# NewPCBMC.net
KiCad netlist of a schematic drawn in Altium Designer
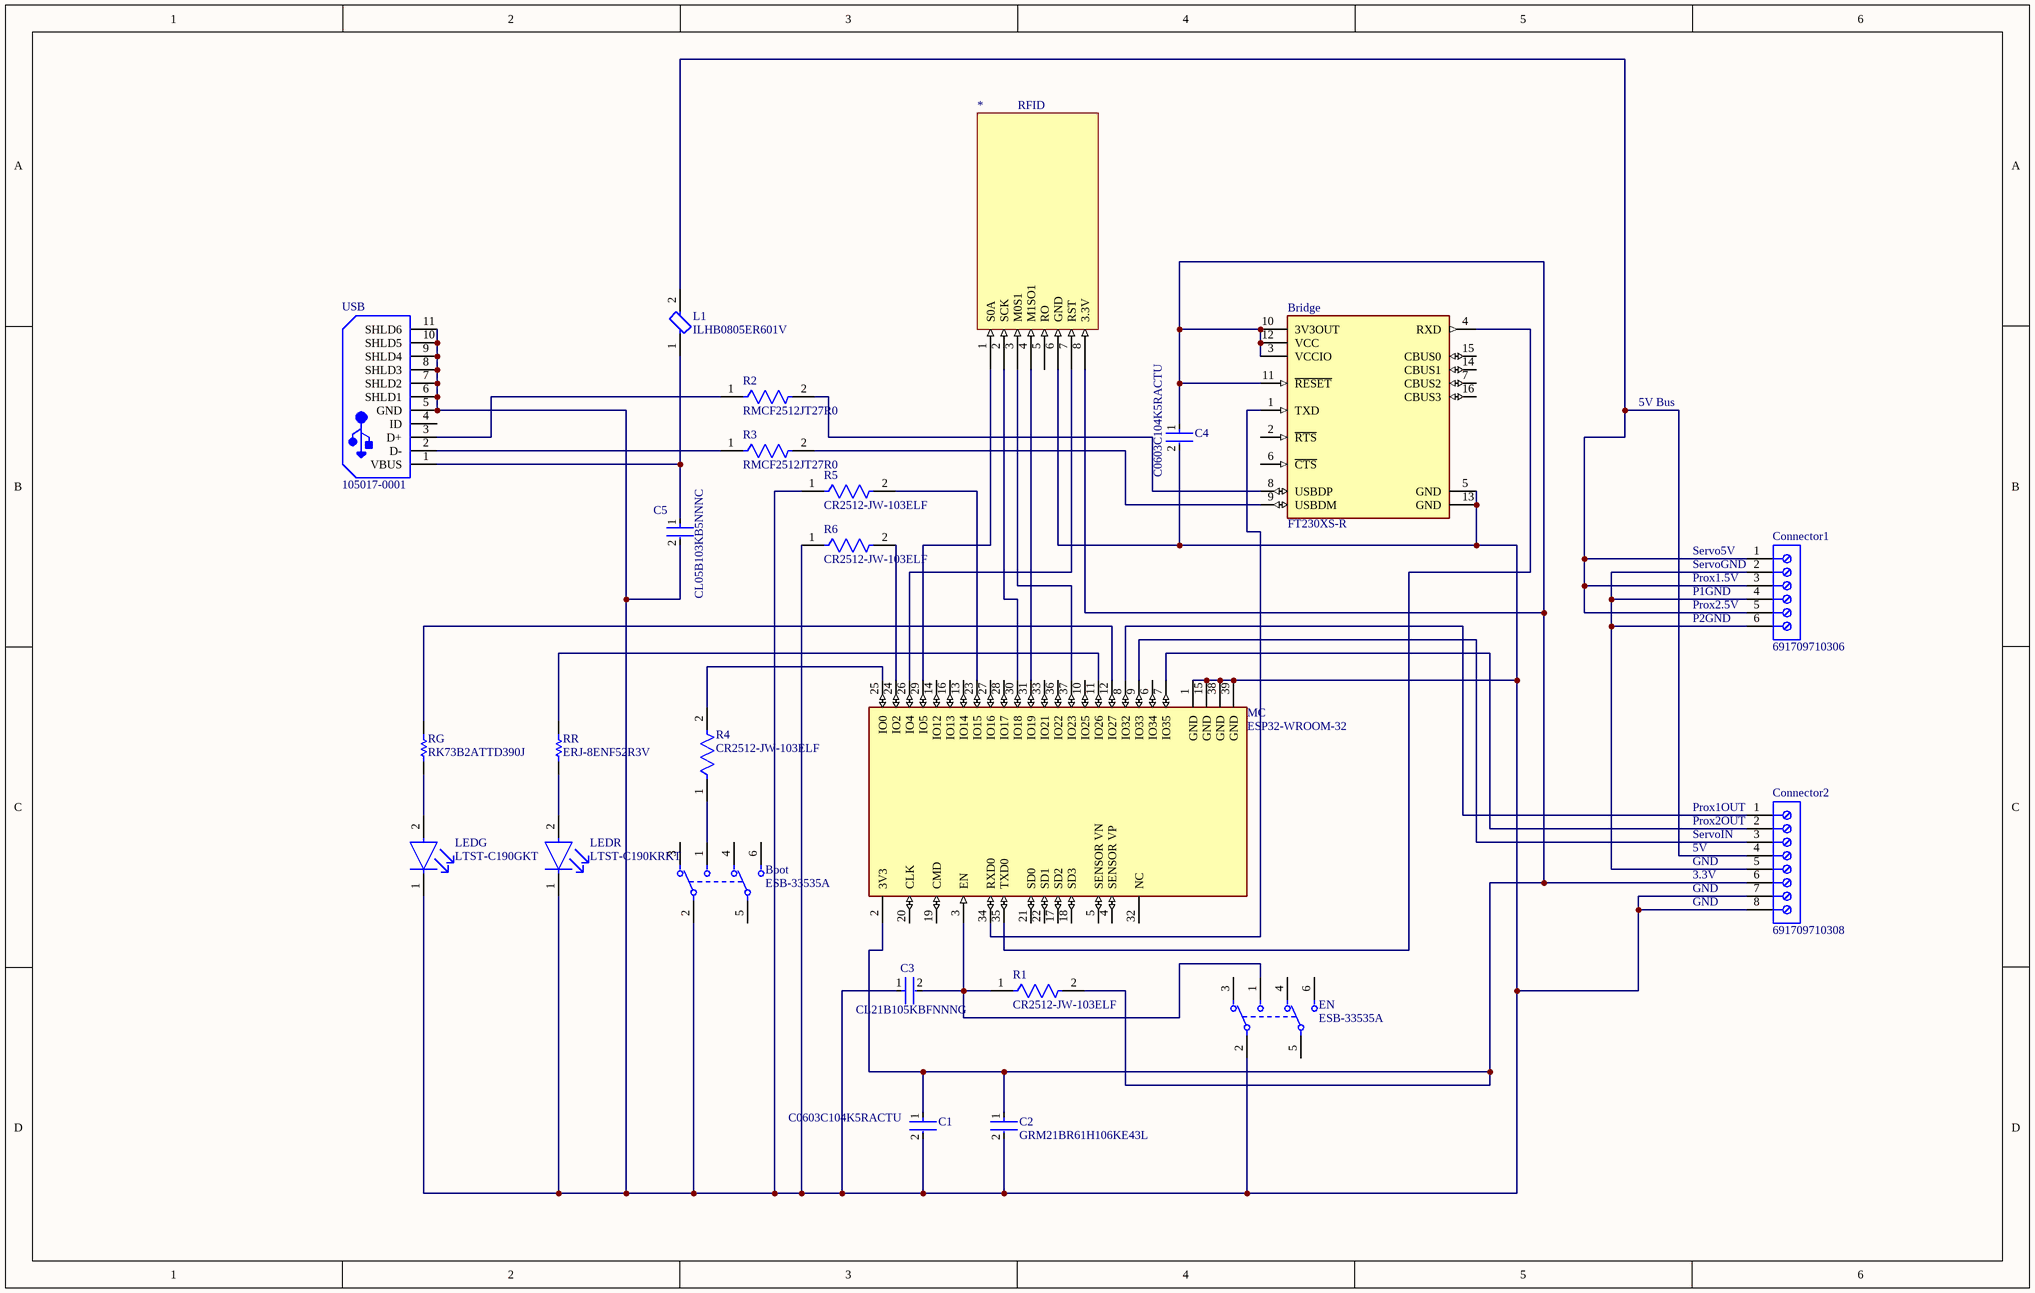
[diagram p0: NewPCBMC.SchDoc]

(export (version "E")
  (design (tool "Eeschema 10.0.6"))
  (components
    (comp (ref "*")
      (value "RFID")
      (footprint "PCBComponent_1")
      (libsource (lib "ProxLibLib") (part "Component_1"))
    )
    (comp (ref "Boot")
      (value "ESB-33535A")
      (footprint "FP-ESB-33535A-MFG")
      (description "SWITCH PUSH DPDT 0.2A 14V")
      (libsource (lib "Altium Content Vault") (part "44dd61f6fe09eb68f0782b479c50d43"))
    )
    (comp (ref "Bridge")
      (value "FT230XS-R")
      (footprint "FP-SSOP-16-MFG")
      (description "IC USB SERIAL BASIC UART 16SSOP")
      (libsource (lib "Altium Content Vault") (part "33f179d67b5e33a3acba2e4c59411a5"))
    )
    (comp (ref "C1")
      (value "C0603C104K5RACTU")
      (footprint "FP-C0603C-CF-MFG")
      (description "CAP CER 0.1UF 50V X7R 0603")
      (fields (field (name "TOLERANCE") "0.1") (field (name "MANUFACTURER") "KEMET"))
      (libsource (lib "Altium Content Vault") (part "b4654b650e69147ec39a6b967a45e02"))
    )
    (comp (ref "C2")
      (value "GRM21BR61H106KE43L")
      (footprint "FP-GRM21B-0_2-e0_2_0_7-IPC_A")
      (description "Chip Multilayer Ceramic Capacitors for General Purpose, 0805, 10uF, X5R, 15%, 10%, 50V")
      (fields (field (name "TOLERANCE") "10%"))
      (libsource (lib "Altium Content Vault") (part "b4654b650e69147ec39a6b967a45e02"))
    )
    (comp (ref "C3")
      (value "CL21B105KBFNNNG")
      (footprint "FP-CL21-IPC_C")
      (description "CL21 Series 0805 1uF 50V ±10% Tolerance X7R Multilayer Ceramic Chip Capacitor")
      (fields (field (name "VOLTAGE") "50V") (field (name "TOLERANCE") "10%"))
      (libsource (lib "Altium Content Vault") (part "b4654b650e69147ec39a6b967a45e02"))
    )
    (comp (ref "C4")
      (value "C0603C104K5RACTU")
      (footprint "FP-C0603C-CF-MFG")
      (description "CAP CER 0.1UF 50V X7R 0603")
      (fields (field (name "TOLERANCE") "0.1") (field (name "MANUFACTURER") "KEMET"))
      (libsource (lib "Altium Content Vault") (part "b4654b650e69147ec39a6b967a45e02"))
    )
    (comp (ref "C5")
      (value "CL05B103KB5NNNC")
      (footprint "FP-CL165-IPC_C")
      (description "Cap Ceramic 10nF 50V X7R ±10% SMD 0402 +125°C Paper T/R")
      (fields (field (name "VOLTAGE") "50V") (field (name "TOLERANCE") "10%"))
      (libsource (lib "Altium Content Vault") (part "b4654b650e69147ec39a6b967a45e02"))
    )
    (comp (ref "Connector1")
      (value "691709710306")
      (footprint "691709710306")
      (fields (field (name "VOLTAGE") "300V"))
      (libsource (lib "Altium Content Vault") (part "TBL - 1R - 06P - Screw"))
    )
    (comp (ref "Connector2")
      (value "691709710308")
      (footprint "691709710308")
      (fields (field (name "VOLTAGE") "300V"))
      (libsource (lib "Altium Content Vault") (part "TBL - 1R - 08P - Screw"))
    )
    (comp (ref "EN")
      (value "ESB-33535A")
      (footprint "FP-ESB-33535A-MFG")
      (description "SWITCH PUSH DPDT 0.2A 14V")
      (libsource (lib "Altium Content Vault") (part "44dd61f6fe09eb68f0782b479c50d43"))
    )
    (comp (ref "L1")
      (value "ILHB0805ER601V")
      (footprint "FP-ILHB-0805-IPC_C")
      (description "FERRITE BEAD 600 OHM 0805 1LN")
      (fields
        (field (name "TOLERANCE") "25%")
        (field (name "OCTOPART") "https://octopart.com/ilhb0805er601v-vishay-39650184")
      )
      (libsource (lib "Altium Content Vault") (part "5f30dd21d616792df468990f7003faa"))
    )
    (comp (ref "LEDG")
      (value "LTST-C190GKT")
      (footprint "FP-LTST-C190GKT-MFG")
      (description "LED GREEN CLEAR CHIP SMD")
      (fields (field (name "VOLTAGE") "2V"))
      (libsource (lib "Altium Content Vault") (part "8706943c75ba83719d021d2fdc84c58"))
    )
    (comp (ref "LEDR")
      (value "LTST-C190KRKT")
      (footprint "FP-LTST-C190KRKT-MFG")
      (description "LED RED CLEAR CHIP SMD")
      (libsource (lib "Altium Content Vault") (part "8706943c75ba83719d021d2fdc84c58"))
    )
    (comp (ref "MC")
      (value "ESP32-WROOM-32")
      (footprint "FP-ESP32-WROOM-32-MFG")
      (description "RX TXRX MOD WIFI SURFACE MOUNT")
      (libsource (lib "Altium Content Vault") (part "ee866abf0b6c51247b7f5cdebf2f250"))
    )
    (comp (ref "R1")
      (value "CR2512-JW-103ELF")
      (footprint "FP-CR2512-IPC_B")
      (description "Thick Film Chip Resistors 2512 10kΩ 1W 5% 200ppm/°C")
      (fields (field (name "TOLERANCE") "5%"))
      (libsource (lib "Altium Content Vault") (part "1029c3af85768c4190bb7ad29bc67b5"))
    )
    (comp (ref "R2")
      (value "RMCF2512JT27R0")
      (footprint "FP-RMCF2512-IPC_B")
      (description "27Ω ±5% 1W 2512 Thick Film Chip Resistor AEC-Q200 compliant")
      (fields (field (name "TOLERANCE") "5%"))
      (libsource (lib "Altium Content Vault") (part "1029c3af85768c4190bb7ad29bc67b5"))
    )
    (comp (ref "R3")
      (value "RMCF2512JT27R0")
      (footprint "FP-RMCF2512-IPC_B")
      (description "27Ω ±5% 1W 2512 Thick Film Chip Resistor AEC-Q200 compliant")
      (fields (field (name "TOLERANCE") "5%"))
      (libsource (lib "Altium Content Vault") (part "1029c3af85768c4190bb7ad29bc67b5"))
    )
    (comp (ref "R4")
      (value "CR2512-JW-103ELF")
      (footprint "FP-CR2512-IPC_B")
      (description "Thick Film Chip Resistors 2512 10kΩ 1W 5% 200ppm/°C")
      (fields (field (name "TOLERANCE") "5%"))
      (libsource (lib "Altium Content Vault") (part "1029c3af85768c4190bb7ad29bc67b5"))
    )
    (comp (ref "R5")
      (value "CR2512-JW-103ELF")
      (footprint "FP-CR2512-IPC_B")
      (description "Thick Film Chip Resistors 2512 10kΩ 1W 5% 200ppm/°C")
      (fields (field (name "TOLERANCE") "5%"))
      (libsource (lib "Altium Content Vault") (part "1029c3af85768c4190bb7ad29bc67b5"))
    )
    (comp (ref "R6")
      (value "CR2512-JW-103ELF")
      (footprint "FP-CR2512-IPC_B")
      (description "Thick Film Chip Resistors 2512 10kΩ 1W 5% 200ppm/°C")
      (fields (field (name "TOLERANCE") "5%"))
      (libsource (lib "Altium Content Vault") (part "1029c3af85768c4190bb7ad29bc67b5"))
    )
    (comp (ref "RG")
      (value "RK73B2ATTD390J")
      (footprint "RESC2013X60X30ML20T20")
      (fields (field (name "MANUFACTURER") "KOA Speer"))
      (libsource (lib "Altium Content Vault") (part "RES"))
    )
    (comp (ref "RR")
      (value "ERJ-8ENF52R3V")
      (footprint "RESC3216X70X50NL05T20")
      (fields (field (name "MANUFACTURER") "Panasonic"))
      (libsource (lib "Altium Content Vault") (part "RES"))
    )
    (comp (ref "USB")
      (value "105017-0001")
      (footprint "USB-MICRO-B_V")
      (fields (field (name "MANUFACTURER") "Molex"))
      (libsource (lib "Altium Content Vault") (part "USB-5-6SHLD"))
    )
  )
  (nets
    (net (code "1") (name "Net-(*-3.3V)") (class "Default")
      (node (ref "*") (pin "8") (pinfunction "3.3V_8") (pintype "input"))
      (node (ref "Bridge") (pin "10") (pinfunction "3V3OUT_10") (pintype "power_in"))
      (node (ref "Bridge") (pin "11") (pinfunction "~{RESET}_11") (pintype "input"))
      (node (ref "Bridge") (pin "12") (pinfunction "VCC_12") (pintype "power_in"))
      (node (ref "Bridge") (pin "3") (pinfunction "VCCIO_3") (pintype "power_in"))
      (node (ref "C1") (pin "1") (pinfunction "1_1") (pintype "passive"))
      (node (ref "C2") (pin "1") (pinfunction "1_1") (pintype "passive"))
      (node (ref "C4") (pin "1") (pinfunction "1_1") (pintype "passive"))
      (node (ref "Connector2") (pin "6") (pinfunction "6_6") (pintype "passive"))
      (node (ref "MC") (pin "2") (pinfunction "3V3_2") (pintype "power_in"))
      (node (ref "R1") (pin "2") (pinfunction "2_2") (pintype "passive"))
    )
    (net (code "2") (name "Net-(*-GND)") (class "Default")
      (node (ref "*") (pin "6") (pinfunction "GND_6") (pintype "input"))
      (node (ref "Boot") (pin "2") (pinfunction "1_C_2") (pintype "passive"))
      (node (ref "Bridge") (pin "13") (pinfunction "GND_13") (pintype "power_in"))
      (node (ref "Bridge") (pin "5") (pinfunction "GND_5") (pintype "power_in"))
      (node (ref "C1") (pin "2") (pinfunction "2_2") (pintype "passive"))
      (node (ref "C2") (pin "2") (pinfunction "2_2") (pintype "passive"))
      (node (ref "C3") (pin "1") (pinfunction "1_1") (pintype "passive"))
      (node (ref "C4") (pin "2") (pinfunction "2_2") (pintype "passive"))
      (node (ref "C5") (pin "2") (pinfunction "2_2") (pintype "passive"))
      (node (ref "Connector2") (pin "7") (pinfunction "7_7") (pintype "passive"))
      (node (ref "Connector2") (pin "8") (pinfunction "8_8") (pintype "passive"))
      (node (ref "EN") (pin "2") (pinfunction "1_C_2") (pintype "passive"))
      (node (ref "LEDG") (pin "1") (pinfunction "C_1") (pintype "passive"))
      (node (ref "LEDR") (pin "1") (pinfunction "C_1") (pintype "passive"))
      (node (ref "MC") (pin "1") (pinfunction "GND_1") (pintype "power_in"))
      (node (ref "MC") (pin "15") (pinfunction "GND_15") (pintype "power_in"))
      (node (ref "MC") (pin "38") (pinfunction "GND_38") (pintype "power_in"))
      (node (ref "MC") (pin "39") (pinfunction "GND_39") (pintype "power_in"))
      (node (ref "R5") (pin "1") (pinfunction "1_1") (pintype "passive"))
      (node (ref "R6") (pin "1") (pinfunction "1_1") (pintype "passive"))
      (node (ref "USB") (pin "10") (pinfunction "SHLD5_10") (pintype "passive"))
      (node (ref "USB") (pin "11") (pinfunction "SHLD6_11") (pintype "passive"))
      (node (ref "USB") (pin "5") (pinfunction "GND_5") (pintype "passive"))
      (node (ref "USB") (pin "6") (pinfunction "SHLD1_6") (pintype "passive"))
      (node (ref "USB") (pin "7") (pinfunction "SHLD2_7") (pintype "passive"))
      (node (ref "USB") (pin "8") (pinfunction "SHLD3_8") (pintype "passive"))
      (node (ref "USB") (pin "9") (pinfunction "SHLD4_9") (pintype "passive"))
    )
    (net (code "3") (name "Net-(*-M0S1)") (class "Default")
      (node (ref "*") (pin "3") (pinfunction "M0S1_3") (pintype "input"))
      (node (ref "MC") (pin "37") (pinfunction "IO23_37") (pintype "bidirectional"))
    )
    (net (code "4") (name "Net-(*-M1SO1)") (class "Default")
      (node (ref "*") (pin "4") (pinfunction "M1SO1_4") (pintype "input"))
      (node (ref "MC") (pin "31") (pinfunction "IO19_31") (pintype "bidirectional"))
    )
    (net (code "5") (name "Net-(*-RST)") (class "Default")
      (node (ref "*") (pin "7") (pinfunction "RST_7") (pintype "input"))
      (node (ref "MC") (pin "26") (pinfunction "IO4_26") (pintype "bidirectional"))
    )
    (net (code "6") (name "Net-(*-S0A)") (class "Default")
      (node (ref "*") (pin "1") (pinfunction "S0A_1") (pintype "input"))
      (node (ref "MC") (pin "29") (pinfunction "IO5_29") (pintype "bidirectional"))
    )
    (net (code "7") (name "Net-(*-SCK)") (class "Default")
      (node (ref "*") (pin "2") (pinfunction "SCK_2") (pintype "input"))
      (node (ref "MC") (pin "30") (pinfunction "IO18_30") (pintype "bidirectional"))
    )
    (net (code "8") (name "Net-(Boot-1_N.O.)") (class "Default")
      (node (ref "Boot") (pin "1") (pinfunction "1_N.O._1") (pintype "passive"))
      (node (ref "R4") (pin "1") (pinfunction "1_1") (pintype "passive"))
    )
    (net (code "9") (name "Net-(Bridge-RXD)") (class "Default")
      (node (ref "Bridge") (pin "4") (pinfunction "RXD_4") (pintype "output"))
      (node (ref "MC") (pin "35") (pinfunction "TXD0_35") (pintype "bidirectional"))
    )
    (net (code "10") (name "Net-(Bridge-TXD)") (class "Default")
      (node (ref "Bridge") (pin "1") (pinfunction "TXD_1") (pintype "input"))
      (node (ref "MC") (pin "34") (pinfunction "RXD0_34") (pintype "bidirectional"))
    )
    (net (code "11") (name "Net-(Bridge-USBDM)") (class "Default")
      (node (ref "Bridge") (pin "9") (pinfunction "USBDM_9") (pintype "bidirectional"))
      (node (ref "R3") (pin "2") (pinfunction "2_2") (pintype "passive"))
    )
    (net (code "12") (name "Net-(Bridge-USBDP)") (class "Default")
      (node (ref "Bridge") (pin "8") (pinfunction "USBDP_8") (pintype "bidirectional"))
      (node (ref "R2") (pin "2") (pinfunction "2_2") (pintype "passive"))
    )
    (net (code "13") (name "Net-(Connector1-Pad1)") (class "Default")
      (node (ref "Connector1") (pin "1") (pinfunction "1_1") (pintype "passive"))
      (node (ref "Connector1") (pin "3") (pinfunction "3_3") (pintype "passive"))
      (node (ref "Connector1") (pin "5") (pinfunction "5_5") (pintype "passive"))
      (node (ref "Connector2") (pin "4") (pinfunction "4_4") (pintype "passive"))
      (node (ref "L1") (pin "2") (pinfunction "2_2") (pintype "passive"))
    )
    (net (code "14") (name "Net-(Connector1-Pad2)") (class "Default")
      (node (ref "Connector1") (pin "2") (pinfunction "2_2") (pintype "passive"))
      (node (ref "Connector1") (pin "4") (pinfunction "4_4") (pintype "passive"))
      (node (ref "Connector1") (pin "6") (pinfunction "6_6") (pintype "passive"))
      (node (ref "Connector2") (pin "5") (pinfunction "5_5") (pintype "passive"))
    )
    (net (code "15") (name "Net-(EN-1_N.O.)") (class "Default")
      (node (ref "C3") (pin "2") (pinfunction "2_2") (pintype "passive"))
      (node (ref "EN") (pin "1") (pinfunction "1_N.O._1") (pintype "passive"))
      (node (ref "MC") (pin "3") (pinfunction "EN_3") (pintype "input"))
      (node (ref "R1") (pin "1") (pinfunction "1_1") (pintype "passive"))
    )
    (net (code "16") (name "Net-(LEDG-A)") (class "Default")
      (node (ref "LEDG") (pin "2") (pinfunction "A_2") (pintype "passive"))
      (node (ref "RG") (pin "1") (pinfunction "1_1") (pintype "passive"))
    )
    (net (code "17") (name "Net-(LEDR-A)") (class "Default")
      (node (ref "LEDR") (pin "2") (pinfunction "A_2") (pintype "passive"))
      (node (ref "RR") (pin "1") (pinfunction "1_1") (pintype "passive"))
    )
    (net (code "18") (name "Net-(MC-IO0)") (class "Default")
      (node (ref "MC") (pin "25") (pinfunction "IO0_25") (pintype "bidirectional"))
      (node (ref "R4") (pin "2") (pinfunction "2_2") (pintype "passive"))
    )
    (net (code "19") (name "Net-(MC-IO2)") (class "Default")
      (node (ref "MC") (pin "24") (pinfunction "IO2_24") (pintype "bidirectional"))
      (node (ref "R6") (pin "2") (pinfunction "2_2") (pintype "passive"))
    )
    (net (code "20") (name "Net-(MC-IO15)") (class "Default")
      (node (ref "MC") (pin "23") (pinfunction "IO15_23") (pintype "bidirectional"))
      (node (ref "R5") (pin "2") (pinfunction "2_2") (pintype "passive"))
    )
    (net (code "21") (name "Net-(MC-IO26)") (class "Default")
      (node (ref "MC") (pin "11") (pinfunction "IO26_11") (pintype "bidirectional"))
      (node (ref "RR") (pin "2") (pinfunction "2_2") (pintype "passive"))
    )
    (net (code "22") (name "Net-(MC-IO27)") (class "Default")
      (node (ref "MC") (pin "12") (pinfunction "IO27_12") (pintype "bidirectional"))
      (node (ref "RG") (pin "2") (pinfunction "2_2") (pintype "passive"))
    )
    (net (code "23") (name "Net-(MC-IO32)") (class "Default")
      (node (ref "Connector2") (pin "1") (pinfunction "1_1") (pintype "passive"))
      (node (ref "MC") (pin "8") (pinfunction "IO32_8") (pintype "bidirectional"))
    )
    (net (code "24") (name "Net-(MC-IO33)") (class "Default")
      (node (ref "Connector2") (pin "3") (pinfunction "3_3") (pintype "passive"))
      (node (ref "MC") (pin "9") (pinfunction "IO33_9") (pintype "bidirectional"))
    )
    (net (code "25") (name "Net-(MC-IO35)") (class "Default")
      (node (ref "Connector2") (pin "2") (pinfunction "2_2") (pintype "passive"))
      (node (ref "MC") (pin "7") (pinfunction "IO35_7") (pintype "bidirectional"))
    )
    (net (code "26") (name "Net-(USB-D+)") (class "Default")
      (node (ref "R2") (pin "1") (pinfunction "1_1") (pintype "passive"))
      (node (ref "USB") (pin "3") (pinfunction "D+_3") (pintype "passive"))
    )
    (net (code "27") (name "Net-(USB-D-)") (class "Default")
      (node (ref "R3") (pin "1") (pinfunction "1_1") (pintype "passive"))
      (node (ref "USB") (pin "2") (pinfunction "D-_2") (pintype "passive"))
    )
    (net (code "28") (name "Net-(USB-VBUS)") (class "Default")
      (node (ref "C5") (pin "1") (pinfunction "1_1") (pintype "passive"))
      (node (ref "L1") (pin "1") (pinfunction "1_1") (pintype "passive"))
      (node (ref "USB") (pin "1") (pinfunction "VBUS_1") (pintype "passive"))
    )
    (net (code "29") (name "unconnected-(*-RO-Pad5)") (class "Default")
      (node (ref "*") (pin "5") (pinfunction "RO_5") (pintype "input"))
    )
    (net (code "30") (name "unconnected-(Boot-1_N.C.-Pad3)") (class "Default")
      (node (ref "Boot") (pin "3") (pinfunction "1_N.C._3") (pintype "passive"))
    )
    (net (code "31") (name "unconnected-(Boot-2_C-Pad5)") (class "Default")
      (node (ref "Boot") (pin "5") (pinfunction "2_C_5") (pintype "passive"))
    )
    (net (code "32") (name "unconnected-(Boot-2_N.C.-Pad4)") (class "Default")
      (node (ref "Boot") (pin "4") (pinfunction "2_N.C._4") (pintype "passive"))
    )
    (net (code "33") (name "unconnected-(Boot-2_N.O.-Pad6)") (class "Default")
      (node (ref "Boot") (pin "6") (pinfunction "2_N.O._6") (pintype "passive"))
    )
    (net (code "34") (name "unconnected-(Bridge-CBUS0-Pad15)") (class "Default")
      (node (ref "Bridge") (pin "15") (pinfunction "CBUS0_15") (pintype "bidirectional"))
    )
    (net (code "35") (name "unconnected-(Bridge-CBUS1-Pad14)") (class "Default")
      (node (ref "Bridge") (pin "14") (pinfunction "CBUS1_14") (pintype "bidirectional"))
    )
    (net (code "36") (name "unconnected-(Bridge-CBUS2-Pad7)") (class "Default")
      (node (ref "Bridge") (pin "7") (pinfunction "CBUS2_7") (pintype "bidirectional"))
    )
    (net (code "37") (name "unconnected-(Bridge-CBUS3-Pad16)") (class "Default")
      (node (ref "Bridge") (pin "16") (pinfunction "CBUS3_16") (pintype "bidirectional"))
    )
    (net (code "38") (name "unconnected-(Bridge-~{CTS}-Pad6)") (class "Default")
      (node (ref "Bridge") (pin "6") (pinfunction "~{CTS}_6") (pintype "input"))
    )
    (net (code "39") (name "unconnected-(Bridge-~{RTS}-Pad2)") (class "Default")
      (node (ref "Bridge") (pin "2") (pinfunction "~{RTS}_2") (pintype "input"))
    )
    (net (code "40") (name "unconnected-(EN-1_N.C.-Pad3)") (class "Default")
      (node (ref "EN") (pin "3") (pinfunction "1_N.C._3") (pintype "passive"))
    )
    (net (code "41") (name "unconnected-(EN-2_C-Pad5)") (class "Default")
      (node (ref "EN") (pin "5") (pinfunction "2_C_5") (pintype "passive"))
    )
    (net (code "42") (name "unconnected-(EN-2_N.C.-Pad4)") (class "Default")
      (node (ref "EN") (pin "4") (pinfunction "2_N.C._4") (pintype "passive"))
    )
    (net (code "43") (name "unconnected-(EN-2_N.O.-Pad6)") (class "Default")
      (node (ref "EN") (pin "6") (pinfunction "2_N.O._6") (pintype "passive"))
    )
    (net (code "44") (name "unconnected-(MC-CLK-Pad20)") (class "Default")
      (node (ref "MC") (pin "20") (pinfunction "CLK_20") (pintype "bidirectional"))
    )
    (net (code "45") (name "unconnected-(MC-CMD-Pad19)") (class "Default")
      (node (ref "MC") (pin "19") (pinfunction "CMD_19") (pintype "bidirectional"))
    )
    (net (code "46") (name "unconnected-(MC-IO12-Pad14)") (class "Default")
      (node (ref "MC") (pin "14") (pinfunction "IO12_14") (pintype "bidirectional"))
    )
    (net (code "47") (name "unconnected-(MC-IO13-Pad16)") (class "Default")
      (node (ref "MC") (pin "16") (pinfunction "IO13_16") (pintype "bidirectional"))
    )
    (net (code "48") (name "unconnected-(MC-IO14-Pad13)") (class "Default")
      (node (ref "MC") (pin "13") (pinfunction "IO14_13") (pintype "bidirectional"))
    )
    (net (code "49") (name "unconnected-(MC-IO16-Pad27)") (class "Default")
      (node (ref "MC") (pin "27") (pinfunction "IO16_27") (pintype "bidirectional"))
    )
    (net (code "50") (name "unconnected-(MC-IO17-Pad28)") (class "Default")
      (node (ref "MC") (pin "28") (pinfunction "IO17_28") (pintype "bidirectional"))
    )
    (net (code "51") (name "unconnected-(MC-IO21-Pad33)") (class "Default")
      (node (ref "MC") (pin "33") (pinfunction "IO21_33") (pintype "bidirectional"))
    )
    (net (code "52") (name "unconnected-(MC-IO22-Pad36)") (class "Default")
      (node (ref "MC") (pin "36") (pinfunction "IO22_36") (pintype "bidirectional"))
    )
    (net (code "53") (name "unconnected-(MC-IO25-Pad10)") (class "Default")
      (node (ref "MC") (pin "10") (pinfunction "IO25_10") (pintype "bidirectional"))
    )
    (net (code "54") (name "unconnected-(MC-IO34-Pad6)") (class "Default")
      (node (ref "MC") (pin "6") (pinfunction "IO34_6") (pintype "bidirectional"))
    )
    (net (code "55") (name "unconnected-(MC-NC-Pad32)") (class "Default")
      (node (ref "MC") (pin "32") (pinfunction "NC_32") (pintype "passive"))
    )
    (net (code "56") (name "unconnected-(MC-SD0-Pad21)") (class "Default")
      (node (ref "MC") (pin "21") (pinfunction "SD0_21") (pintype "bidirectional"))
    )
    (net (code "57") (name "unconnected-(MC-SD1-Pad22)") (class "Default")
      (node (ref "MC") (pin "22") (pinfunction "SD1_22") (pintype "bidirectional"))
    )
    (net (code "58") (name "unconnected-(MC-SD2-Pad17)") (class "Default")
      (node (ref "MC") (pin "17") (pinfunction "SD2_17") (pintype "bidirectional"))
    )
    (net (code "59") (name "unconnected-(MC-SD3-Pad18)") (class "Default")
      (node (ref "MC") (pin "18") (pinfunction "SD3_18") (pintype "bidirectional"))
    )
    (net (code "60") (name "unconnected-(MC-SENSOR_VN-Pad5)") (class "Default")
      (node (ref "MC") (pin "5") (pinfunction "SENSOR_VN_5") (pintype "bidirectional"))
    )
    (net (code "61") (name "unconnected-(MC-SENSOR_VP-Pad4)") (class "Default")
      (node (ref "MC") (pin "4") (pinfunction "SENSOR_VP_4") (pintype "bidirectional"))
    )
    (net (code "62") (name "unconnected-(USB-ID-Pad4)") (class "Default")
      (node (ref "USB") (pin "4") (pinfunction "ID_4") (pintype "passive"))
    )
  )
)
